# breakout_v1_1.net
KiCad netlist of a schematic drawn in EAGLE
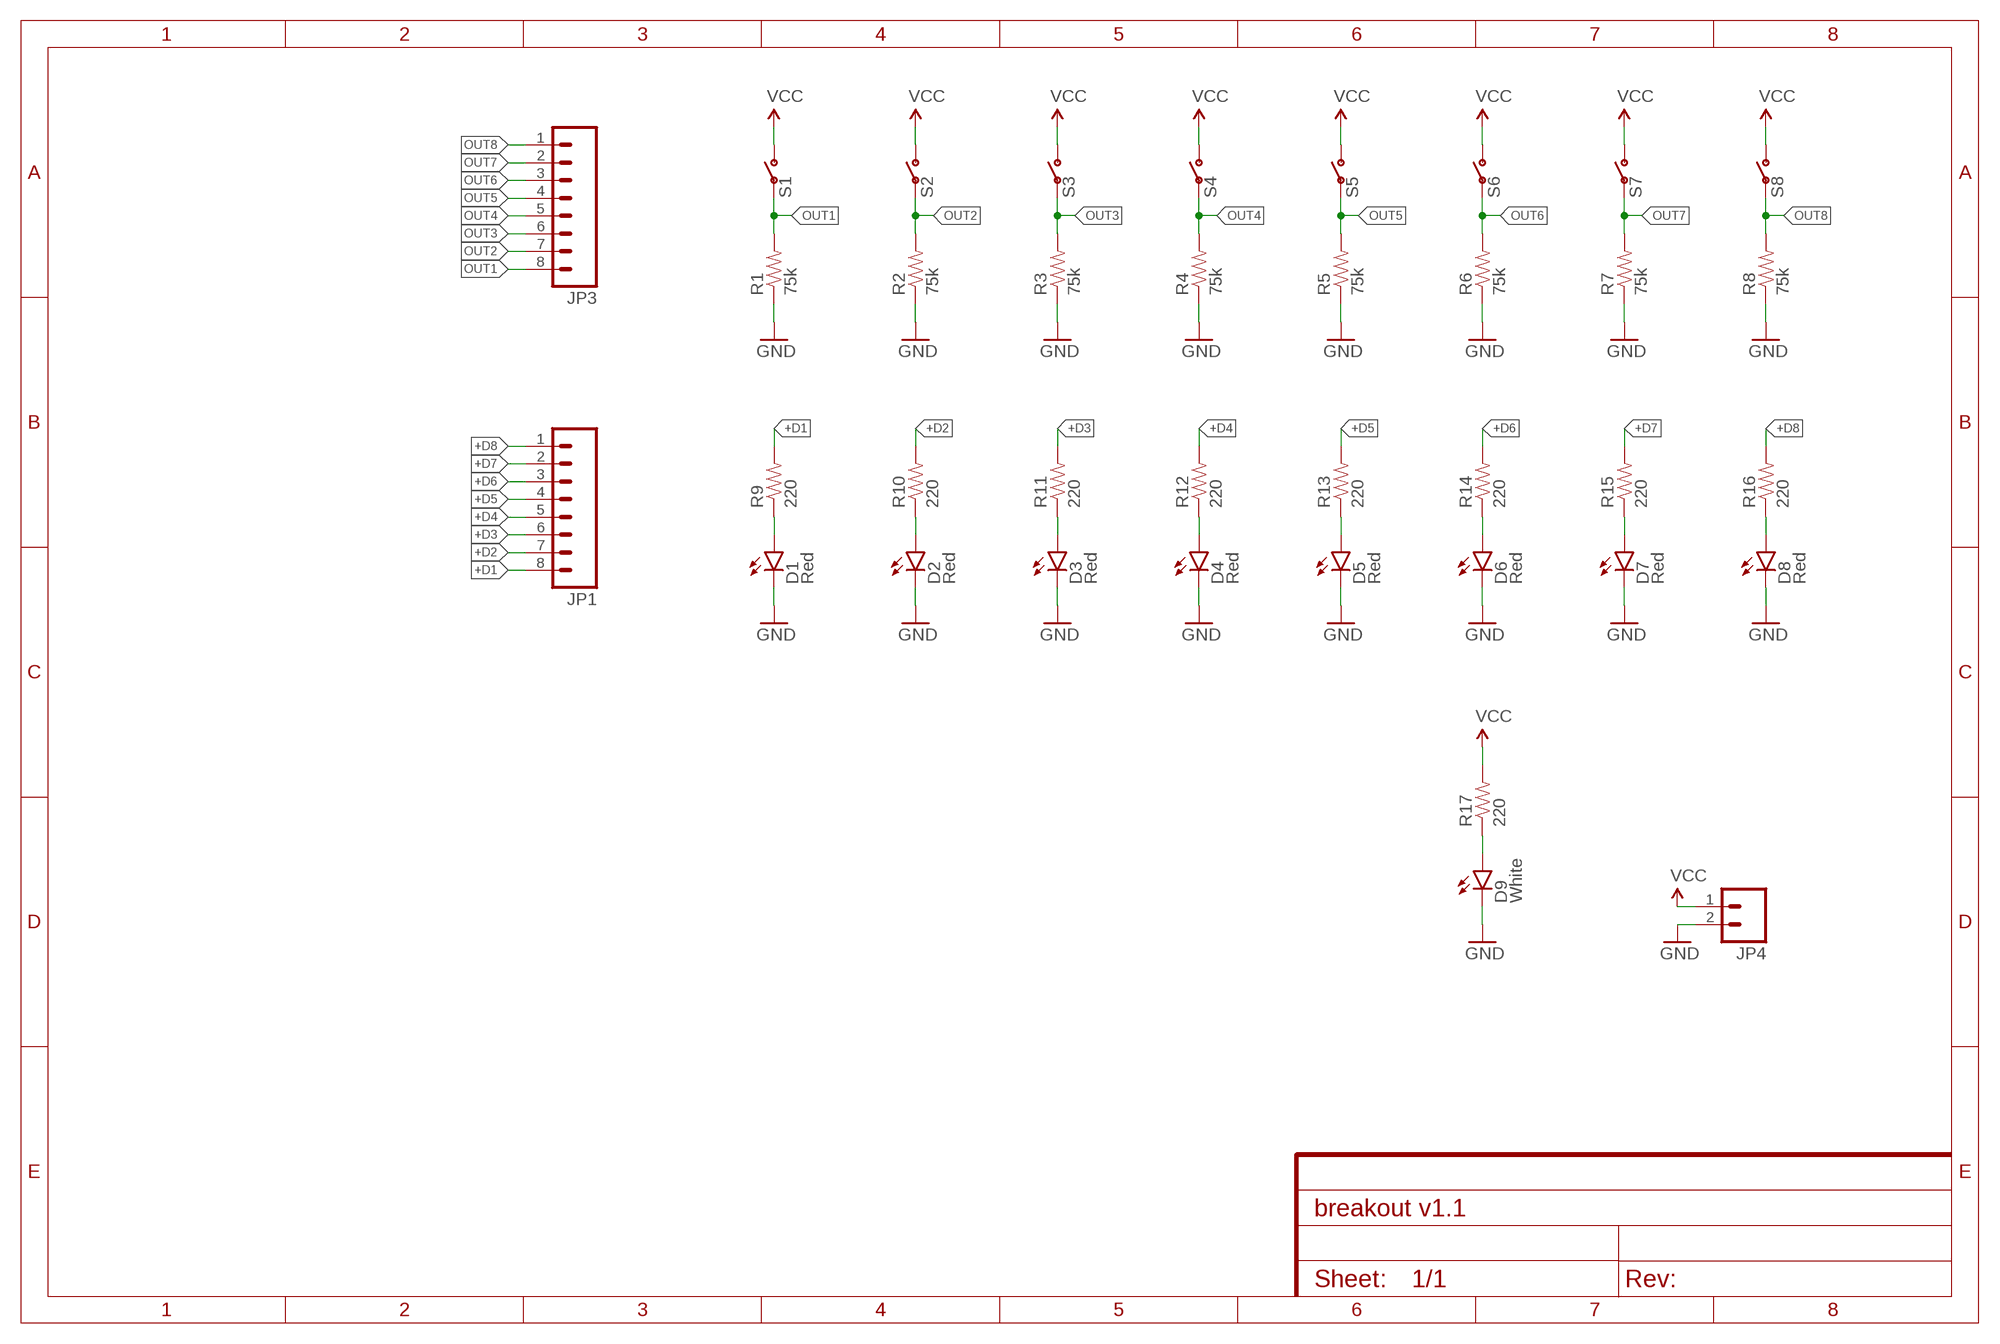
[diagram p0: schematic, sheet 1]

(export (version "E")
  (design (tool "Eeschema 10.0.6"))
  (components
    (comp (ref "D1")
      (value "Red")
      (footprint "eagle-import:0805")
      (libsource (lib "eagle-import") (part "LED0805"))
    )
    (comp (ref "D2")
      (value "Red")
      (footprint "eagle-import:0805")
      (libsource (lib "eagle-import") (part "LED0805"))
    )
    (comp (ref "D3")
      (value "Red")
      (footprint "eagle-import:0805")
      (libsource (lib "eagle-import") (part "LED0805"))
    )
    (comp (ref "D4")
      (value "Red")
      (footprint "eagle-import:0805")
      (libsource (lib "eagle-import") (part "LED0805"))
    )
    (comp (ref "D5")
      (value "Red")
      (footprint "eagle-import:0805")
      (libsource (lib "eagle-import") (part "LED0805"))
    )
    (comp (ref "D6")
      (value "Red")
      (footprint "eagle-import:0805")
      (libsource (lib "eagle-import") (part "LED0805"))
    )
    (comp (ref "D7")
      (value "Red")
      (footprint "eagle-import:0805")
      (libsource (lib "eagle-import") (part "LED0805"))
    )
    (comp (ref "D8")
      (value "Red")
      (footprint "eagle-import:0805")
      (libsource (lib "eagle-import") (part "LED0805"))
    )
    (comp (ref "D9")
      (value "White")
      (footprint "eagle-import:LED-0603")
      (libsource (lib "eagle-import") (part "LED0603"))
    )
    (comp (ref "JP1")
      (value "M08")
      (footprint "eagle-import:1X08_ROUND")
      (libsource (lib "eagle-import") (part "M08"))
    )
    (comp (ref "JP3")
      (value "M08")
      (footprint "eagle-import:1X08_ROUND")
      (libsource (lib "eagle-import") (part "M08"))
    )
    (comp (ref "JP4")
      (value "M02PTH")
      (footprint "eagle-import:1X02")
      (libsource (lib "eagle-import") (part "M02PTH"))
    )
    (comp (ref "R1")
      (value "75k")
      (footprint "eagle-import:0805")
      (libsource (lib "eagle-import") (part "RESISTOR0805-RES"))
    )
    (comp (ref "R2")
      (value "75k")
      (footprint "eagle-import:0805")
      (libsource (lib "eagle-import") (part "RESISTOR0805-RES"))
    )
    (comp (ref "R3")
      (value "75k")
      (footprint "eagle-import:0805")
      (libsource (lib "eagle-import") (part "RESISTOR0805-RES"))
    )
    (comp (ref "R4")
      (value "75k")
      (footprint "eagle-import:0805")
      (libsource (lib "eagle-import") (part "RESISTOR0805-RES"))
    )
    (comp (ref "R5")
      (value "75k")
      (footprint "eagle-import:0805")
      (libsource (lib "eagle-import") (part "RESISTOR0805-RES"))
    )
    (comp (ref "R6")
      (value "75k")
      (footprint "eagle-import:0805")
      (libsource (lib "eagle-import") (part "RESISTOR0805-RES"))
    )
    (comp (ref "R7")
      (value "75k")
      (footprint "eagle-import:0805")
      (libsource (lib "eagle-import") (part "RESISTOR0805-RES"))
    )
    (comp (ref "R8")
      (value "75k")
      (footprint "eagle-import:0805")
      (libsource (lib "eagle-import") (part "RESISTOR0805-RES"))
    )
    (comp (ref "R9")
      (value "220")
      (footprint "eagle-import:0805")
      (libsource (lib "eagle-import") (part "RESISTOR0805-RES"))
    )
    (comp (ref "R10")
      (value "220")
      (footprint "eagle-import:0805")
      (libsource (lib "eagle-import") (part "RESISTOR0805-RES"))
    )
    (comp (ref "R11")
      (value "220")
      (footprint "eagle-import:0805")
      (libsource (lib "eagle-import") (part "RESISTOR0805-RES"))
    )
    (comp (ref "R12")
      (value "220")
      (footprint "eagle-import:0805")
      (libsource (lib "eagle-import") (part "RESISTOR0805-RES"))
    )
    (comp (ref "R13")
      (value "220")
      (footprint "eagle-import:0805")
      (libsource (lib "eagle-import") (part "RESISTOR0805-RES"))
    )
    (comp (ref "R14")
      (value "220")
      (footprint "eagle-import:0805")
      (libsource (lib "eagle-import") (part "RESISTOR0805-RES"))
    )
    (comp (ref "R15")
      (value "220")
      (footprint "eagle-import:0805")
      (libsource (lib "eagle-import") (part "RESISTOR0805-RES"))
    )
    (comp (ref "R16")
      (value "220")
      (footprint "eagle-import:0805")
      (libsource (lib "eagle-import") (part "RESISTOR0805-RES"))
    )
    (comp (ref "R17")
      (value "220")
      (footprint "eagle-import:0805")
      (libsource (lib "eagle-import") (part "RESISTOR0805-RES"))
    )
    (comp (ref "S1")
      (value "SWITCH_SPSTSMD")
      (footprint "eagle-import:5.2X5.2X1.5-SMD")
      (libsource (lib "eagle-import") (part "SWITCH_SPSTSMD"))
    )
    (comp (ref "S2")
      (value "SWITCH_SPSTSMD")
      (footprint "eagle-import:5.2X5.2X1.5-SMD")
      (libsource (lib "eagle-import") (part "SWITCH_SPSTSMD"))
    )
    (comp (ref "S3")
      (value "SWITCH_SPSTSMD")
      (footprint "eagle-import:5.2X5.2X1.5-SMD")
      (libsource (lib "eagle-import") (part "SWITCH_SPSTSMD"))
    )
    (comp (ref "S4")
      (value "SWITCH_SPSTSMD")
      (footprint "eagle-import:5.2X5.2X1.5-SMD")
      (libsource (lib "eagle-import") (part "SWITCH_SPSTSMD"))
    )
    (comp (ref "S5")
      (value "SWITCH_SPSTSMD")
      (footprint "eagle-import:5.2X5.2X1.5-SMD")
      (libsource (lib "eagle-import") (part "SWITCH_SPSTSMD"))
    )
    (comp (ref "S6")
      (value "SWITCH_SPSTSMD")
      (footprint "eagle-import:5.2X5.2X1.5-SMD")
      (libsource (lib "eagle-import") (part "SWITCH_SPSTSMD"))
    )
    (comp (ref "S7")
      (value "SWITCH_SPSTSMD")
      (footprint "eagle-import:5.2X5.2X1.5-SMD")
      (libsource (lib "eagle-import") (part "SWITCH_SPSTSMD"))
    )
    (comp (ref "S8")
      (value "SWITCH_SPSTSMD")
      (footprint "eagle-import:5.2X5.2X1.5-SMD")
      (libsource (lib "eagle-import") (part "SWITCH_SPSTSMD"))
    )
  )
  (nets
    (net (code "1") (name "+D1") (class "Default")
      (node (ref "JP1") (pin "8") (pinfunction "8_8") (pintype "passive"))
      (node (ref "R9") (pin "2") (pinfunction "2_2") (pintype "passive"))
    )
    (net (code "2") (name "+D2") (class "Default")
      (node (ref "JP1") (pin "7") (pinfunction "7_7") (pintype "passive"))
      (node (ref "R10") (pin "2") (pinfunction "2_2") (pintype "passive"))
    )
    (net (code "3") (name "+D3") (class "Default")
      (node (ref "JP1") (pin "6") (pinfunction "6_6") (pintype "passive"))
      (node (ref "R11") (pin "2") (pinfunction "2_2") (pintype "passive"))
    )
    (net (code "4") (name "+D4") (class "Default")
      (node (ref "JP1") (pin "5") (pinfunction "5_5") (pintype "passive"))
      (node (ref "R12") (pin "2") (pinfunction "2_2") (pintype "passive"))
    )
    (net (code "5") (name "+D5") (class "Default")
      (node (ref "JP1") (pin "4") (pinfunction "4_4") (pintype "passive"))
      (node (ref "R13") (pin "2") (pinfunction "2_2") (pintype "passive"))
    )
    (net (code "6") (name "+D6") (class "Default")
      (node (ref "JP1") (pin "3") (pinfunction "3_3") (pintype "passive"))
      (node (ref "R14") (pin "2") (pinfunction "2_2") (pintype "passive"))
    )
    (net (code "7") (name "+D7") (class "Default")
      (node (ref "JP1") (pin "2") (pinfunction "2_2") (pintype "passive"))
      (node (ref "R15") (pin "2") (pinfunction "2_2") (pintype "passive"))
    )
    (net (code "8") (name "+D8") (class "Default")
      (node (ref "JP1") (pin "1") (pinfunction "1_1") (pintype "passive"))
      (node (ref "R16") (pin "2") (pinfunction "2_2") (pintype "passive"))
    )
    (net (code "9") (name "GND") (class "Default")
      (node (ref "D1") (pin "2") (pinfunction "C_2") (pintype "passive"))
      (node (ref "D2") (pin "2") (pinfunction "C_2") (pintype "passive"))
      (node (ref "D3") (pin "2") (pinfunction "C_2") (pintype "passive"))
      (node (ref "D4") (pin "2") (pinfunction "C_2") (pintype "passive"))
      (node (ref "D5") (pin "2") (pinfunction "C_2") (pintype "passive"))
      (node (ref "D6") (pin "2") (pinfunction "C_2") (pintype "passive"))
      (node (ref "D7") (pin "2") (pinfunction "C_2") (pintype "passive"))
      (node (ref "D8") (pin "2") (pinfunction "C_2") (pintype "passive"))
      (node (ref "D9") (pin "C") (pinfunction "C_C") (pintype "passive"))
      (node (ref "JP4") (pin "2") (pinfunction "2_2") (pintype "passive"))
      (node (ref "R1") (pin "1") (pinfunction "1_1") (pintype "passive"))
      (node (ref "R2") (pin "1") (pinfunction "1_1") (pintype "passive"))
      (node (ref "R3") (pin "1") (pinfunction "1_1") (pintype "passive"))
      (node (ref "R4") (pin "1") (pinfunction "1_1") (pintype "passive"))
      (node (ref "R5") (pin "1") (pinfunction "1_1") (pintype "passive"))
      (node (ref "R6") (pin "1") (pinfunction "1_1") (pintype "passive"))
      (node (ref "R7") (pin "1") (pinfunction "1_1") (pintype "passive"))
      (node (ref "R8") (pin "1") (pinfunction "1_1") (pintype "passive"))
    )
    (net (code "10") (name "Net-(D1-A)") (class "Default")
      (node (ref "D1") (pin "1") (pinfunction "A_1") (pintype "passive"))
      (node (ref "R9") (pin "1") (pinfunction "1_1") (pintype "passive"))
    )
    (net (code "11") (name "Net-(D2-A)") (class "Default")
      (node (ref "D2") (pin "1") (pinfunction "A_1") (pintype "passive"))
      (node (ref "R10") (pin "1") (pinfunction "1_1") (pintype "passive"))
    )
    (net (code "12") (name "Net-(D3-A)") (class "Default")
      (node (ref "D3") (pin "1") (pinfunction "A_1") (pintype "passive"))
      (node (ref "R11") (pin "1") (pinfunction "1_1") (pintype "passive"))
    )
    (net (code "13") (name "Net-(D4-A)") (class "Default")
      (node (ref "D4") (pin "1") (pinfunction "A_1") (pintype "passive"))
      (node (ref "R12") (pin "1") (pinfunction "1_1") (pintype "passive"))
    )
    (net (code "14") (name "Net-(D5-A)") (class "Default")
      (node (ref "D5") (pin "1") (pinfunction "A_1") (pintype "passive"))
      (node (ref "R13") (pin "1") (pinfunction "1_1") (pintype "passive"))
    )
    (net (code "15") (name "Net-(D6-A)") (class "Default")
      (node (ref "D6") (pin "1") (pinfunction "A_1") (pintype "passive"))
      (node (ref "R14") (pin "1") (pinfunction "1_1") (pintype "passive"))
    )
    (net (code "16") (name "Net-(D7-A)") (class "Default")
      (node (ref "D7") (pin "1") (pinfunction "A_1") (pintype "passive"))
      (node (ref "R15") (pin "1") (pinfunction "1_1") (pintype "passive"))
    )
    (net (code "17") (name "Net-(D8-A)") (class "Default")
      (node (ref "D8") (pin "1") (pinfunction "A_1") (pintype "passive"))
      (node (ref "R16") (pin "1") (pinfunction "1_1") (pintype "passive"))
    )
    (net (code "18") (name "Net-(D9-PadA)") (class "Default")
      (node (ref "D9") (pin "A") (pinfunction "A_A") (pintype "passive"))
      (node (ref "R17") (pin "1") (pinfunction "1_1") (pintype "passive"))
    )
    (net (code "19") (name "OUT1") (class "Default")
      (node (ref "JP3") (pin "8") (pinfunction "8_8") (pintype "passive"))
      (node (ref "R1") (pin "2") (pinfunction "2_2") (pintype "passive"))
      (node (ref "S1") (pin "P$3") (pinfunction "2_P$3") (pintype "bidirectional"))
    )
    (net (code "20") (name "OUT2") (class "Default")
      (node (ref "JP3") (pin "7") (pinfunction "7_7") (pintype "passive"))
      (node (ref "R2") (pin "2") (pinfunction "2_2") (pintype "passive"))
      (node (ref "S2") (pin "P$3") (pinfunction "2_P$3") (pintype "bidirectional"))
    )
    (net (code "21") (name "OUT3") (class "Default")
      (node (ref "JP3") (pin "6") (pinfunction "6_6") (pintype "passive"))
      (node (ref "R3") (pin "2") (pinfunction "2_2") (pintype "passive"))
      (node (ref "S3") (pin "P$3") (pinfunction "2_P$3") (pintype "bidirectional"))
    )
    (net (code "22") (name "OUT4") (class "Default")
      (node (ref "JP3") (pin "5") (pinfunction "5_5") (pintype "passive"))
      (node (ref "R4") (pin "2") (pinfunction "2_2") (pintype "passive"))
      (node (ref "S4") (pin "P$3") (pinfunction "2_P$3") (pintype "bidirectional"))
    )
    (net (code "23") (name "OUT5") (class "Default")
      (node (ref "JP3") (pin "4") (pinfunction "4_4") (pintype "passive"))
      (node (ref "R5") (pin "2") (pinfunction "2_2") (pintype "passive"))
      (node (ref "S5") (pin "P$3") (pinfunction "2_P$3") (pintype "bidirectional"))
    )
    (net (code "24") (name "OUT6") (class "Default")
      (node (ref "JP3") (pin "3") (pinfunction "3_3") (pintype "passive"))
      (node (ref "R6") (pin "2") (pinfunction "2_2") (pintype "passive"))
      (node (ref "S6") (pin "P$3") (pinfunction "2_P$3") (pintype "bidirectional"))
    )
    (net (code "25") (name "OUT7") (class "Default")
      (node (ref "JP3") (pin "2") (pinfunction "2_2") (pintype "passive"))
      (node (ref "R7") (pin "2") (pinfunction "2_2") (pintype "passive"))
      (node (ref "S7") (pin "P$3") (pinfunction "2_P$3") (pintype "bidirectional"))
    )
    (net (code "26") (name "OUT8") (class "Default")
      (node (ref "JP3") (pin "1") (pinfunction "1_1") (pintype "passive"))
      (node (ref "R8") (pin "2") (pinfunction "2_2") (pintype "passive"))
      (node (ref "S8") (pin "P$3") (pinfunction "2_P$3") (pintype "bidirectional"))
    )
    (net (code "27") (name "VCC") (class "Default")
      (node (ref "JP4") (pin "1") (pinfunction "1_1") (pintype "passive"))
      (node (ref "R17") (pin "2") (pinfunction "2_2") (pintype "passive"))
      (node (ref "S1") (pin "P$1") (pinfunction "1_P$1") (pintype "bidirectional"))
      (node (ref "S2") (pin "P$1") (pinfunction "1_P$1") (pintype "bidirectional"))
      (node (ref "S3") (pin "P$1") (pinfunction "1_P$1") (pintype "bidirectional"))
      (node (ref "S4") (pin "P$1") (pinfunction "1_P$1") (pintype "bidirectional"))
      (node (ref "S5") (pin "P$1") (pinfunction "1_P$1") (pintype "bidirectional"))
      (node (ref "S6") (pin "P$1") (pinfunction "1_P$1") (pintype "bidirectional"))
      (node (ref "S7") (pin "P$1") (pinfunction "1_P$1") (pintype "bidirectional"))
      (node (ref "S8") (pin "P$1") (pinfunction "1_P$1") (pintype "bidirectional"))
    )
  )
)
